# RC-Stepper.net
KiCad netlist of a schematic drawn in EAGLE
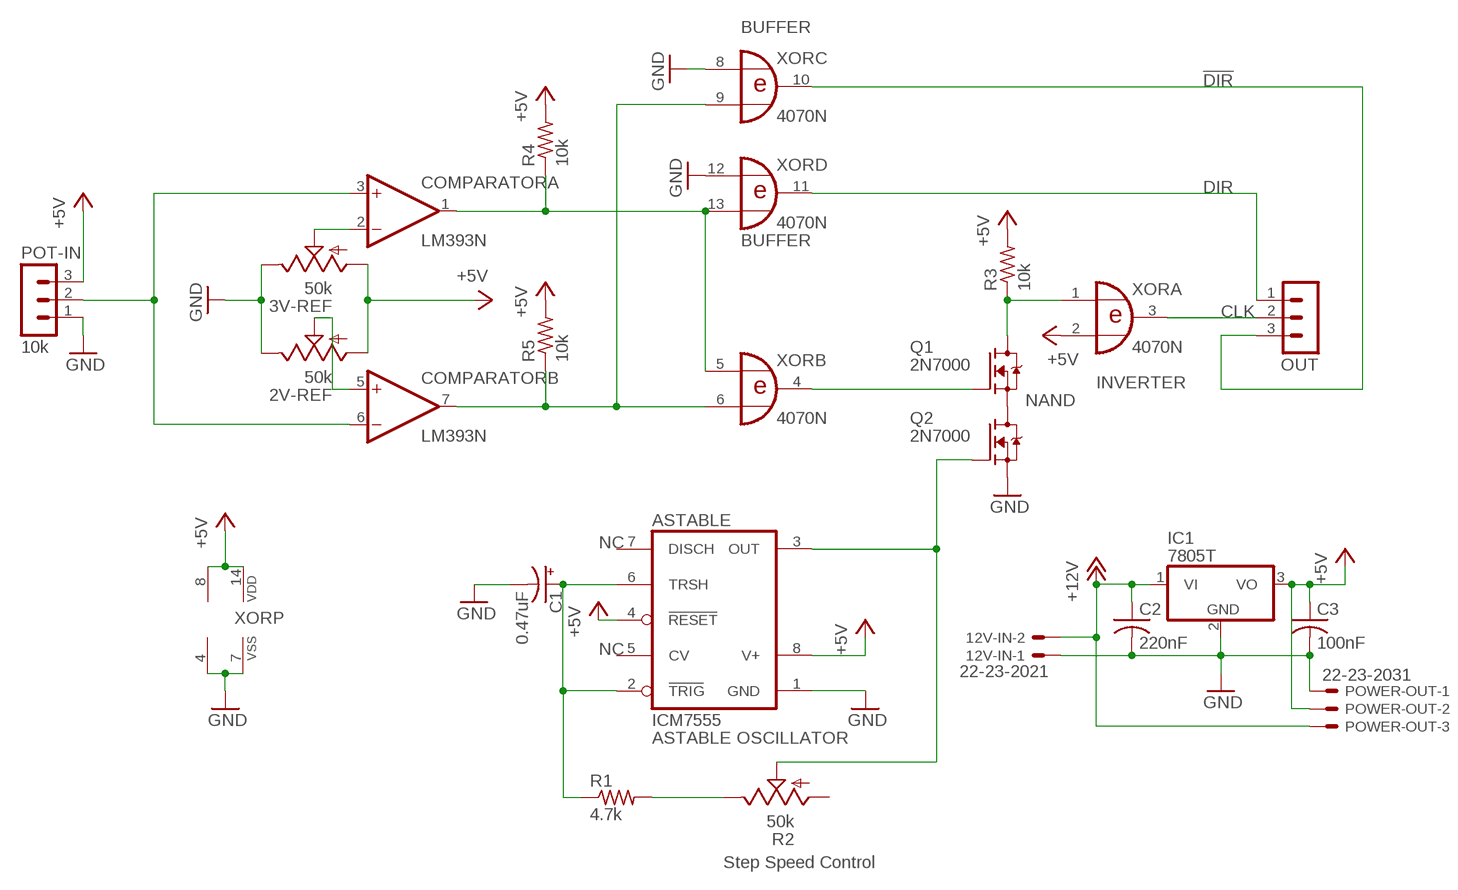
[diagram p0: schematic, sheet 1]

(export (version "E")
  (design (tool "Eeschema 10.0.6"))
  (components
    (comp (ref "2V-REF")
      (value "50k")
      (footprint "eagle-import:PT-SPIN")
      (libsource (lib "eagle-import") (part "TRIM_US-PT-SPIN"))
    )
    (comp (ref "3V-REF")
      (value "50k")
      (footprint "eagle-import:PT-SPIN")
      (libsource (lib "eagle-import") (part "TRIM_US-PT-SPIN"))
    )
    (comp (ref "12V-IN")
      (value "22-23-2021")
      (footprint "eagle-import:22-23-2021")
      (fields (field (name "MF") "MOLEX"))
      (libsource (lib "eagle-import") (part "22-23-2021"))
    )
    (comp (ref "ASTABLE")
      (value "ICM7555")
      (footprint "eagle-import:DIL08")
      (fields (field (name "MF") "MAXIM") (field (name "MPN") "ICM7555IPA+"))
      (libsource (lib "eagle-import") (part "ICM7555"))
    )
    (comp (ref "C1")
      (value "0.47uF")
      (footprint "eagle-import:E2,5-6")
      (libsource (lib "eagle-import") (part "CPOL-USE2.5-6"))
    )
    (comp (ref "C2")
      (value "220nF")
      (footprint "eagle-import:C025-030X050")
      (libsource (lib "eagle-import") (part "C-US025-030X050"))
    )
    (comp (ref "C3")
      (value "100nF")
      (footprint "eagle-import:C025-030X050")
      (libsource (lib "eagle-import") (part "C-US025-030X050"))
    )
    (comp (ref "COMPARATOR")
      (value "LM393N")
      (footprint "eagle-import:DIL08")
      (libsource (lib "eagle-import") (part "LM393N"))
    )
    (comp (ref "IC1")
      (value "7805T")
      (footprint "eagle-import:TO220H")
      (libsource (lib "eagle-import") (part "78T05"))
    )
    (comp (ref "OUT")
      (value "MA03-1")
      (footprint "eagle-import:MA03-1")
      (libsource (lib "eagle-import") (part "MA03-1"))
    )
    (comp (ref "POT-IN")
      (value "10k")
      (footprint "eagle-import:MA03-1")
      (libsource (lib "eagle-import") (part "MA03-1"))
    )
    (comp (ref "POWER-OUT")
      (value "22-23-2031")
      (footprint "eagle-import:22-23-2031")
      (fields (field (name "MF") "MOLEX"))
      (libsource (lib "eagle-import") (part "22-23-2031"))
    )
    (comp (ref "Q1")
      (value "2N7000")
      (footprint "eagle-import:TO92-")
      (libsource (lib "eagle-import") (part "2N7000"))
    )
    (comp (ref "Q2")
      (value "2N7000")
      (footprint "eagle-import:TO92-")
      (libsource (lib "eagle-import") (part "2N7000"))
    )
    (comp (ref "R1")
      (value "4.7k")
      (footprint "eagle-import:0204_7")
      (libsource (lib "eagle-import") (part "R-US_0204/7"))
    )
    (comp (ref "R2")
      (value "50k")
      (footprint "eagle-import:B25P")
      (libsource (lib "eagle-import") (part "TRIM_US-B25P"))
    )
    (comp (ref "R3")
      (value "10k")
      (footprint "eagle-import:0204_7")
      (libsource (lib "eagle-import") (part "R-US_0204/7"))
    )
    (comp (ref "R4")
      (value "10k")
      (footprint "eagle-import:0204_7")
      (libsource (lib "eagle-import") (part "R-US_0204/7"))
    )
    (comp (ref "R5")
      (value "10k")
      (footprint "eagle-import:0204_7")
      (libsource (lib "eagle-import") (part "R-US_0204/7"))
    )
    (comp (ref "XOR")
      (value "4070N")
      (footprint "eagle-import:DIL14")
      (libsource (lib "eagle-import") (part "4070N"))
    )
  )
  (nets
    (net (code "1") (name "+5V") (class "Default")
      (node (ref "2V-REF") (pin "A") (pinfunction "A_A") (pintype "passive"))
      (node (ref "3V-REF") (pin "A") (pinfunction "A_A") (pintype "passive"))
      (node (ref "ASTABLE") (pin "4") (pinfunction "RESET_4") (pintype "input"))
      (node (ref "ASTABLE") (pin "8") (pinfunction "V+_8") (pintype "power_in"))
      (node (ref "C3") (pin "1") (pinfunction "1_1") (pintype "passive"))
      (node (ref "COMPARATOR") (pin "8") (pinfunction "V+_8") (pintype "power_in"))
      (node (ref "IC1") (pin "3") (pinfunction "VO_3") (pintype "passive"))
      (node (ref "POT-IN") (pin "3") (pinfunction "3_3") (pintype "passive"))
      (node (ref "POWER-OUT") (pin "2") (pinfunction "S_2") (pintype "passive"))
      (node (ref "R3") (pin "2") (pinfunction "2_2") (pintype "passive"))
      (node (ref "R4") (pin "2") (pinfunction "2_2") (pintype "passive"))
      (node (ref "R5") (pin "2") (pinfunction "2_2") (pintype "passive"))
      (node (ref "XOR") (pin "14") (pinfunction "VDD_14") (pintype "power_in"))
      (node (ref "XOR") (pin "2") (pinfunction "I1_2") (pintype "input"))
    )
    (net (code "2") (name "+12V") (class "Default")
      (node (ref "12V-IN") (pin "2") (pinfunction "S_2") (pintype "passive"))
      (node (ref "C2") (pin "1") (pinfunction "1_1") (pintype "passive"))
      (node (ref "IC1") (pin "1") (pinfunction "VI_1") (pintype "input"))
      (node (ref "POWER-OUT") (pin "3") (pinfunction "S_3") (pintype "passive"))
    )
    (net (code "3") (name "GND") (class "Default")
      (node (ref "12V-IN") (pin "1") (pinfunction "S_1") (pintype "passive"))
      (node (ref "2V-REF") (pin "E") (pinfunction "E_E") (pintype "passive"))
      (node (ref "3V-REF") (pin "E") (pinfunction "E_E") (pintype "passive"))
      (node (ref "ASTABLE") (pin "1") (pinfunction "GND_1") (pintype "power_in"))
      (node (ref "C1") (pin "-") (pinfunction "-_-") (pintype "passive"))
      (node (ref "C2") (pin "2") (pinfunction "2_2") (pintype "passive"))
      (node (ref "C3") (pin "2") (pinfunction "2_2") (pintype "passive"))
      (node (ref "COMPARATOR") (pin "4") (pinfunction "V-_4") (pintype "power_in"))
      (node (ref "IC1") (pin "2") (pinfunction "GND_2") (pintype "passive"))
      (node (ref "POT-IN") (pin "1") (pinfunction "1_1") (pintype "passive"))
      (node (ref "POWER-OUT") (pin "1") (pinfunction "S_1") (pintype "passive"))
      (node (ref "Q2") (pin "3") (pinfunction "S_3") (pintype "passive"))
      (node (ref "XOR") (pin "12") (pinfunction "I0_12") (pintype "input"))
      (node (ref "XOR") (pin "7") (pinfunction "VSS_7") (pintype "power_in"))
      (node (ref "XOR") (pin "8") (pinfunction "I0_8") (pintype "input"))
    )
    (net (code "4") (name "Net-(ASTABLE-OUT)") (class "Default")
      (node (ref "ASTABLE") (pin "3") (pinfunction "OUT_3") (pintype "output"))
      (node (ref "Q2") (pin "2") (pinfunction "G_2") (pintype "passive"))
      (node (ref "R2") (pin "S") (pinfunction "S_S") (pintype "passive"))
    )
    (net (code "5") (name "Net-(ASTABLE-TRIG)") (class "Default")
      (node (ref "ASTABLE") (pin "2") (pinfunction "TRIG_2") (pintype "bidirectional"))
      (node (ref "ASTABLE") (pin "6") (pinfunction "TRSH_6") (pintype "input"))
      (node (ref "C1") (pin "+") (pinfunction "+_+") (pintype "passive"))
      (node (ref "R1") (pin "1") (pinfunction "1_1") (pintype "passive"))
    )
    (net (code "6") (name "Net-(COMPARATORA-+IN)") (class "Default")
      (node (ref "COMPARATOR") (pin "3") (pinfunction "+IN_3") (pintype "input"))
      (node (ref "COMPARATOR") (pin "6") (pinfunction "-IN_6") (pintype "input"))
      (node (ref "POT-IN") (pin "2") (pinfunction "2_2") (pintype "passive"))
    )
    (net (code "7") (name "Net-(COMPARATORA--IN)") (class "Default")
      (node (ref "3V-REF") (pin "S") (pinfunction "S_S") (pintype "passive"))
      (node (ref "COMPARATOR") (pin "2") (pinfunction "-IN_2") (pintype "input"))
    )
    (net (code "8") (name "Net-(COMPARATORA-OUT)") (class "Default")
      (node (ref "COMPARATOR") (pin "1") (pinfunction "OUT_1") (pintype "output"))
      (node (ref "R4") (pin "1") (pinfunction "1_1") (pintype "passive"))
      (node (ref "XOR") (pin "13") (pinfunction "I1_13") (pintype "input"))
      (node (ref "XOR") (pin "5") (pinfunction "I0_5") (pintype "input"))
    )
    (net (code "9") (name "Net-(COMPARATORB-+IN)") (class "Default")
      (node (ref "2V-REF") (pin "S") (pinfunction "S_S") (pintype "passive"))
      (node (ref "COMPARATOR") (pin "5") (pinfunction "+IN_5") (pintype "input"))
    )
    (net (code "10") (name "Net-(COMPARATORB-OUT)") (class "Default")
      (node (ref "COMPARATOR") (pin "7") (pinfunction "OUT_7") (pintype "output"))
      (node (ref "R5") (pin "1") (pinfunction "1_1") (pintype "passive"))
      (node (ref "XOR") (pin "6") (pinfunction "I1_6") (pintype "input"))
      (node (ref "XOR") (pin "9") (pinfunction "I1_9") (pintype "input"))
    )
    (net (code "11") (name "Net-(Q1-D)") (class "Default")
      (node (ref "Q1") (pin "1") (pinfunction "D_1") (pintype "passive"))
      (node (ref "R3") (pin "1") (pinfunction "1_1") (pintype "passive"))
      (node (ref "XOR") (pin "1") (pinfunction "I0_1") (pintype "input"))
    )
    (net (code "12") (name "Net-(Q1-G)") (class "Default")
      (node (ref "Q1") (pin "2") (pinfunction "G_2") (pintype "passive"))
      (node (ref "XOR") (pin "4") (pinfunction "O_4") (pintype "output"))
    )
    (net (code "13") (name "Net-(Q1-S)") (class "Default")
      (node (ref "Q1") (pin "3") (pinfunction "S_3") (pintype "passive"))
      (node (ref "Q2") (pin "1") (pinfunction "D_1") (pintype "passive"))
    )
    (net (code "14") (name "Net-(R1-Pad2)") (class "Default")
      (node (ref "R1") (pin "2") (pinfunction "2_2") (pintype "passive"))
      (node (ref "R2") (pin "E") (pinfunction "E_E") (pintype "passive"))
    )
    (net (code "15") (name "Net-(XORA-O)") (class "Default")
      (node (ref "OUT") (pin "2") (pinfunction "2_2") (pintype "passive"))
      (node (ref "XOR") (pin "3") (pinfunction "O_3") (pintype "output"))
    )
    (net (code "16") (name "Net-(XORC-O)") (class "Default")
      (node (ref "OUT") (pin "3") (pinfunction "3_3") (pintype "passive"))
      (node (ref "XOR") (pin "10") (pinfunction "O_10") (pintype "output"))
    )
    (net (code "17") (name "Net-(XORD-O)") (class "Default")
      (node (ref "OUT") (pin "1") (pinfunction "1_1") (pintype "passive"))
      (node (ref "XOR") (pin "11") (pinfunction "O_11") (pintype "output"))
    )
    (net (code "18") (name "unconnected-(ASTABLE-CV-Pad5)") (class "Default")
      (node (ref "ASTABLE") (pin "5") (pinfunction "CV_5") (pintype "passive"))
    )
    (net (code "19") (name "unconnected-(ASTABLE-DISCH-Pad7)") (class "Default")
      (node (ref "ASTABLE") (pin "7") (pinfunction "DISCH_7") (pintype "input"))
    )
    (net (code "20") (name "unconnected-(R2-PadA)") (class "Default")
      (node (ref "R2") (pin "A") (pinfunction "A_A") (pintype "passive"))
    )
  )
)
